# Wall_plug.net
KiCad netlist of a schematic drawn in EAGLE
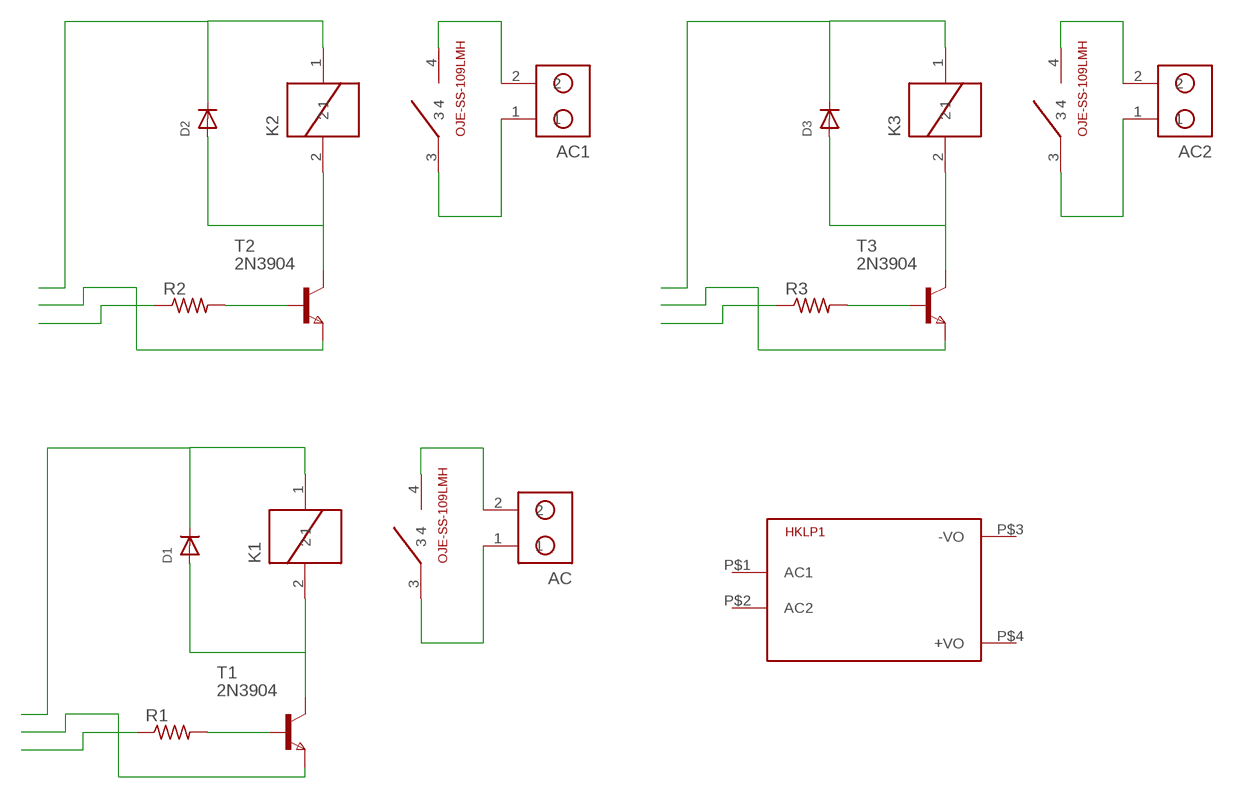
[diagram p0: schematic, sheet 1]

(export (version "E")
  (design (tool "Eeschema 10.0.6"))
  (components
    (comp (ref "AC")
      (value "TBLOCK1X2")
      (footprint "eagle-import:TBLOCK1X2")
      (libsource (lib "eagle-import") (part "TBLOCK1X2"))
    )
    (comp (ref "AC1")
      (value "TBLOCK1X2")
      (footprint "eagle-import:TBLOCK1X2")
      (libsource (lib "eagle-import") (part "TBLOCK1X2"))
    )
    (comp (ref "AC2")
      (value "TBLOCK1X2")
      (footprint "eagle-import:TBLOCK1X2")
      (libsource (lib "eagle-import") (part "TBLOCK1X2"))
    )
    (comp (ref "D1")
      (value "DIODESMA")
      (footprint "eagle-import:SMADIODE")
      (libsource (lib "eagle-import") (part "DIODESMA"))
    )
    (comp (ref "D2")
      (value "DIODESMA")
      (footprint "eagle-import:SMADIODE")
      (libsource (lib "eagle-import") (part "DIODESMA"))
    )
    (comp (ref "D3")
      (value "DIODESMA")
      (footprint "eagle-import:SMADIODE")
      (libsource (lib "eagle-import") (part "DIODESMA"))
    )
    (comp (ref "HKLP1")
      (value "HKLPM01")
      (footprint "eagle-import:HKLPM01")
      (libsource (lib "eagle-import") (part "HKLPM01"))
    )
    (comp (ref "K1")
      (value "OJE-SS-109LMH")
      (footprint "eagle-import:OJE-SS-109LMH")
      (libsource (lib "eagle-import") (part "OJE-SS-109LMH"))
    )
    (comp (ref "K2")
      (value "OJE-SS-109LMH")
      (footprint "eagle-import:OJE-SS-109LMH")
      (libsource (lib "eagle-import") (part "OJE-SS-109LMH"))
    )
    (comp (ref "K3")
      (value "OJE-SS-109LMH")
      (footprint "eagle-import:OJE-SS-109LMH")
      (libsource (lib "eagle-import") (part "OJE-SS-109LMH"))
    )
    (comp (ref "R1")
      (value "R-US_R0603")
      (footprint "eagle-import:R0603")
      (libsource (lib "eagle-import") (part "R-US_R0603"))
    )
    (comp (ref "R2")
      (value "R-US_R0603")
      (footprint "eagle-import:R0603")
      (libsource (lib "eagle-import") (part "R-US_R0603"))
    )
    (comp (ref "R3")
      (value "R-US_R0603")
      (footprint "eagle-import:R0603")
      (libsource (lib "eagle-import") (part "R-US_R0603"))
    )
    (comp (ref "T1")
      (value "2N3904")
      (footprint "eagle-import:SOT-23")
      (libsource (lib "eagle-import") (part "FMMT451"))
    )
    (comp (ref "T2")
      (value "2N3904")
      (footprint "eagle-import:SOT-23")
      (libsource (lib "eagle-import") (part "FMMT451"))
    )
    (comp (ref "T3")
      (value "2N3904")
      (footprint "eagle-import:SOT-23")
      (libsource (lib "eagle-import") (part "FMMT451"))
    )
  )
  (nets
    (net (code "1") (name "Net-(AC-Pad1)") (class "Default")
      (node (ref "AC") (pin "1") (pinfunction "1_1") (pintype "bidirectional"))
      (node (ref "K1") (pin "3") (pinfunction "3_3") (pintype "bidirectional"))
    )
    (net (code "2") (name "Net-(AC-Pad2)") (class "Default")
      (node (ref "AC") (pin "2") (pinfunction "2_2") (pintype "bidirectional"))
      (node (ref "K1") (pin "4") (pinfunction "4_4") (pintype "bidirectional"))
    )
    (net (code "3") (name "Net-(AC1-Pad1)") (class "Default")
      (node (ref "AC1") (pin "1") (pinfunction "1_1") (pintype "bidirectional"))
      (node (ref "K2") (pin "3") (pinfunction "3_3") (pintype "bidirectional"))
    )
    (net (code "4") (name "Net-(AC1-Pad2)") (class "Default")
      (node (ref "AC1") (pin "2") (pinfunction "2_2") (pintype "bidirectional"))
      (node (ref "K2") (pin "4") (pinfunction "4_4") (pintype "bidirectional"))
    )
    (net (code "5") (name "Net-(AC2-Pad1)") (class "Default")
      (node (ref "AC2") (pin "1") (pinfunction "1_1") (pintype "bidirectional"))
      (node (ref "K3") (pin "3") (pinfunction "3_3") (pintype "bidirectional"))
    )
    (net (code "6") (name "Net-(AC2-Pad2)") (class "Default")
      (node (ref "AC2") (pin "2") (pinfunction "2_2") (pintype "bidirectional"))
      (node (ref "K3") (pin "4") (pinfunction "4_4") (pintype "bidirectional"))
    )
    (net (code "7") (name "Net-(D1-PadC)") (class "Default")
      (node (ref "D1") (pin "C") (pinfunction "C_C") (pintype "passive"))
      (node (ref "K1") (pin "1") (pinfunction "1_1") (pintype "bidirectional"))
    )
    (net (code "8") (name "Net-(D2-PadC)") (class "Default")
      (node (ref "D2") (pin "C") (pinfunction "C_C") (pintype "passive"))
      (node (ref "K2") (pin "1") (pinfunction "1_1") (pintype "bidirectional"))
    )
    (net (code "9") (name "Net-(D3-PadC)") (class "Default")
      (node (ref "D3") (pin "C") (pinfunction "C_C") (pintype "passive"))
      (node (ref "K3") (pin "1") (pinfunction "1_1") (pintype "bidirectional"))
    )
    (net (code "10") (name "Net-(T1-B)") (class "Default")
      (node (ref "R1") (pin "2") (pinfunction "2_2") (pintype "passive"))
      (node (ref "T1") (pin "3") (pinfunction "B_3") (pintype "passive"))
    )
    (net (code "11") (name "Net-(T1-C)") (class "Default")
      (node (ref "D1") (pin "A") (pinfunction "A_A") (pintype "passive"))
      (node (ref "K1") (pin "2") (pinfunction "2_2") (pintype "bidirectional"))
      (node (ref "T1") (pin "1") (pinfunction "C_1") (pintype "passive"))
    )
    (net (code "12") (name "Net-(T2-B)") (class "Default")
      (node (ref "R2") (pin "2") (pinfunction "2_2") (pintype "passive"))
      (node (ref "T2") (pin "3") (pinfunction "B_3") (pintype "passive"))
    )
    (net (code "13") (name "Net-(T2-C)") (class "Default")
      (node (ref "D2") (pin "A") (pinfunction "A_A") (pintype "passive"))
      (node (ref "K2") (pin "2") (pinfunction "2_2") (pintype "bidirectional"))
      (node (ref "T2") (pin "1") (pinfunction "C_1") (pintype "passive"))
    )
    (net (code "14") (name "Net-(T3-B)") (class "Default")
      (node (ref "R3") (pin "2") (pinfunction "2_2") (pintype "passive"))
      (node (ref "T3") (pin "3") (pinfunction "B_3") (pintype "passive"))
    )
    (net (code "15") (name "Net-(T3-C)") (class "Default")
      (node (ref "D3") (pin "A") (pinfunction "A_A") (pintype "passive"))
      (node (ref "K3") (pin "2") (pinfunction "2_2") (pintype "bidirectional"))
      (node (ref "T3") (pin "1") (pinfunction "C_1") (pintype "passive"))
    )
    (net (code "16") (name "unconnected-(HKLP1-+VO-PadP$4)") (class "Default")
      (node (ref "HKLP1") (pin "P$4") (pinfunction "+VO_P$4") (pintype "bidirectional"))
    )
    (net (code "17") (name "unconnected-(HKLP1--VO-PadP$3)") (class "Default")
      (node (ref "HKLP1") (pin "P$3") (pinfunction "-VO_P$3") (pintype "bidirectional"))
    )
    (net (code "18") (name "unconnected-(HKLP1-AC1-PadP$1)") (class "Default")
      (node (ref "HKLP1") (pin "P$1") (pinfunction "AC1_P$1") (pintype "bidirectional"))
    )
    (net (code "19") (name "unconnected-(HKLP1-AC2-PadP$2)") (class "Default")
      (node (ref "HKLP1") (pin "P$2") (pinfunction "AC2_P$2") (pintype "bidirectional"))
    )
    (net (code "20") (name "unconnected-(R1-Pad1)") (class "Default")
      (node (ref "R1") (pin "1") (pinfunction "1_1") (pintype "passive"))
    )
    (net (code "21") (name "unconnected-(R2-Pad1)") (class "Default")
      (node (ref "R2") (pin "1") (pinfunction "1_1") (pintype "passive"))
    )
    (net (code "22") (name "unconnected-(R3-Pad1)") (class "Default")
      (node (ref "R3") (pin "1") (pinfunction "1_1") (pintype "passive"))
    )
    (net (code "23") (name "unconnected-(T1-E-Pad2)") (class "Default")
      (node (ref "T1") (pin "2") (pinfunction "E_2") (pintype "passive"))
    )
    (net (code "24") (name "unconnected-(T2-E-Pad2)") (class "Default")
      (node (ref "T2") (pin "2") (pinfunction "E_2") (pintype "passive"))
    )
    (net (code "25") (name "unconnected-(T3-E-Pad2)") (class "Default")
      (node (ref "T3") (pin "2") (pinfunction "E_2") (pintype "passive"))
    )
  )
)
